# clock.net
KiCad netlist of a schematic drawn in EAGLE
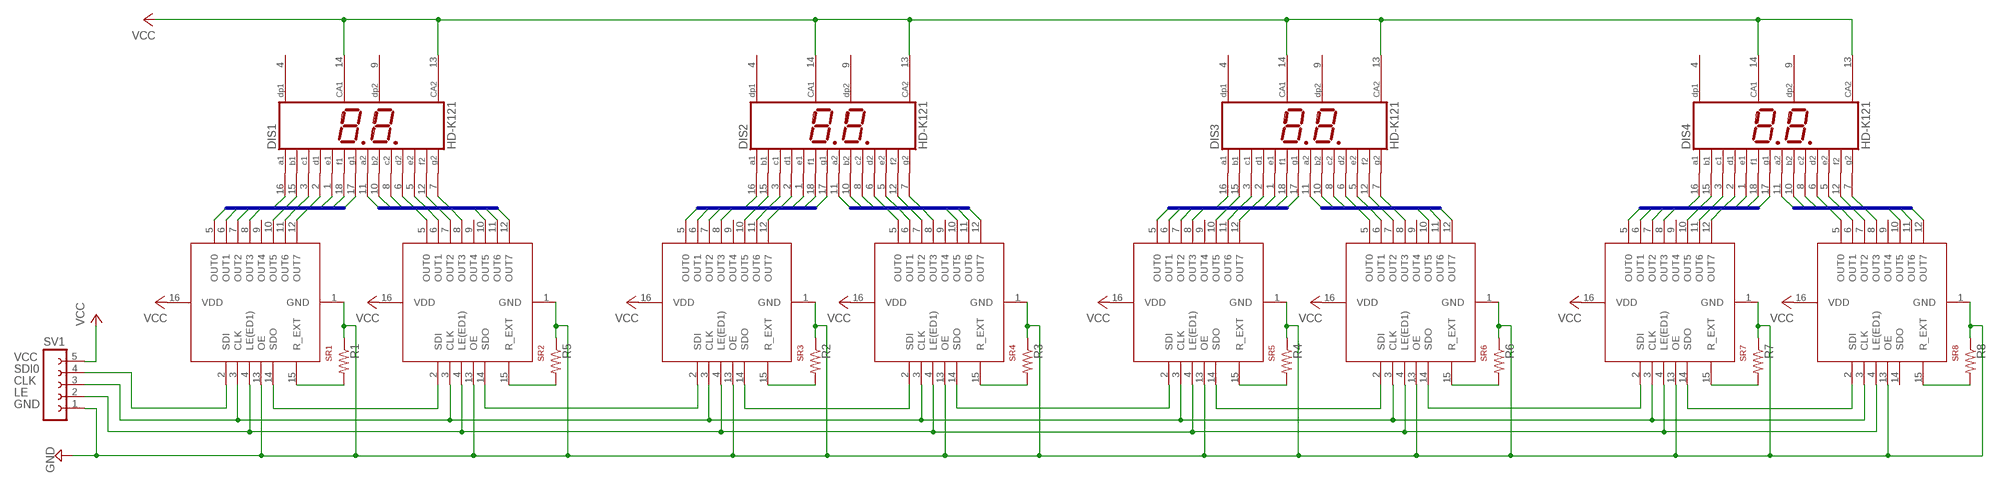
[diagram p0: schematic, sheet 1]

(export (version "E")
  (design (tool "Eeschema 10.0.6"))
  (components
    (comp (ref "DIS1")
      (value "HD-K121")
      (footprint "eagle-import:HDSP-R")
      (libsource (lib "eagle-import") (part "HD-K121"))
    )
    (comp (ref "DIS2")
      (value "HD-K121")
      (footprint "eagle-import:HDSP-R")
      (libsource (lib "eagle-import") (part "HD-K121"))
    )
    (comp (ref "DIS3")
      (value "HD-K121")
      (footprint "eagle-import:HDSP-R")
      (libsource (lib "eagle-import") (part "HD-K121"))
    )
    (comp (ref "DIS4")
      (value "HD-K121")
      (footprint "eagle-import:HDSP-R")
      (libsource (lib "eagle-import") (part "HD-K121"))
    )
    (comp (ref "R1")
      (value "R-US_R0603")
      (footprint "eagle-import:R0603")
      (libsource (lib "eagle-import") (part "R-US_R0603"))
    )
    (comp (ref "R2")
      (value "R-US_R0603")
      (footprint "eagle-import:R0603")
      (libsource (lib "eagle-import") (part "R-US_R0603"))
    )
    (comp (ref "R3")
      (value "R-US_R0603")
      (footprint "eagle-import:R0603")
      (libsource (lib "eagle-import") (part "R-US_R0603"))
    )
    (comp (ref "R4")
      (value "R-US_R0603")
      (footprint "eagle-import:R0603")
      (libsource (lib "eagle-import") (part "R-US_R0603"))
    )
    (comp (ref "R5")
      (value "R-US_R0603")
      (footprint "eagle-import:R0603")
      (libsource (lib "eagle-import") (part "R-US_R0603"))
    )
    (comp (ref "R6")
      (value "R-US_R0603")
      (footprint "eagle-import:R0603")
      (libsource (lib "eagle-import") (part "R-US_R0603"))
    )
    (comp (ref "R7")
      (value "R-US_R0603")
      (footprint "eagle-import:R0603")
      (libsource (lib "eagle-import") (part "R-US_R0603"))
    )
    (comp (ref "R8")
      (value "R-US_R0603")
      (footprint "eagle-import:R0603")
      (libsource (lib "eagle-import") (part "R-US_R0603"))
    )
    (comp (ref "SR1")
      (value "TLC5916/17")
      (footprint "eagle-import:SOIC-16")
      (libsource (lib "eagle-import") (part "TLC5916/17"))
    )
    (comp (ref "SR2")
      (value "TLC5916/17")
      (footprint "eagle-import:SOIC-16")
      (libsource (lib "eagle-import") (part "TLC5916/17"))
    )
    (comp (ref "SR3")
      (value "TLC5916/17")
      (footprint "eagle-import:SOIC-16")
      (libsource (lib "eagle-import") (part "TLC5916/17"))
    )
    (comp (ref "SR4")
      (value "TLC5916/17")
      (footprint "eagle-import:SOIC-16")
      (libsource (lib "eagle-import") (part "TLC5916/17"))
    )
    (comp (ref "SR5")
      (value "TLC5916/17")
      (footprint "eagle-import:SOIC-16")
      (libsource (lib "eagle-import") (part "TLC5916/17"))
    )
    (comp (ref "SR6")
      (value "TLC5916/17")
      (footprint "eagle-import:SOIC-16")
      (libsource (lib "eagle-import") (part "TLC5916/17"))
    )
    (comp (ref "SR7")
      (value "TLC5916/17")
      (footprint "eagle-import:SOIC-16")
      (libsource (lib "eagle-import") (part "TLC5916/17"))
    )
    (comp (ref "SR8")
      (value "TLC5916/17")
      (footprint "eagle-import:SOIC-16")
      (libsource (lib "eagle-import") (part "TLC5916/17"))
    )
    (comp (ref "SV1")
      (value "FE05-1")
      (footprint "eagle-import:FE05-1")
      (libsource (lib "eagle-import") (part "FE05-1"))
    )
  )
  (nets
    (net (code "1") (name "/CLK") (class "Default")
      (node (ref "SR1") (pin "3") (pinfunction "CLK_3") (pintype "bidirectional"))
      (node (ref "SR2") (pin "3") (pinfunction "CLK_3") (pintype "bidirectional"))
      (node (ref "SR3") (pin "3") (pinfunction "CLK_3") (pintype "bidirectional"))
      (node (ref "SR4") (pin "3") (pinfunction "CLK_3") (pintype "bidirectional"))
      (node (ref "SR5") (pin "3") (pinfunction "CLK_3") (pintype "bidirectional"))
      (node (ref "SR6") (pin "3") (pinfunction "CLK_3") (pintype "bidirectional"))
      (node (ref "SR7") (pin "3") (pinfunction "CLK_3") (pintype "bidirectional"))
      (node (ref "SR8") (pin "3") (pinfunction "CLK_3") (pintype "bidirectional"))
      (node (ref "SV1") (pin "3") (pinfunction "3_3") (pintype "passive"))
    )
    (net (code "2") (name "/DAYSONES0") (class "Default")
      (node (ref "DIS1") (pin "11") (pinfunction "A2_11") (pintype "passive"))
      (node (ref "SR2") (pin "11") (pinfunction "OUT6_11") (pintype "bidirectional"))
    )
    (net (code "3") (name "/DAYSONES1") (class "Default")
      (node (ref "DIS1") (pin "10") (pinfunction "B2_10") (pintype "passive"))
      (node (ref "SR2") (pin "12") (pinfunction "OUT7_12") (pintype "bidirectional"))
    )
    (net (code "4") (name "/DAYSONES2") (class "Default")
      (node (ref "DIS1") (pin "8") (pinfunction "C2_8") (pintype "passive"))
      (node (ref "SR2") (pin "5") (pinfunction "OUT0_5") (pintype "bidirectional"))
    )
    (net (code "5") (name "/DAYSONES3") (class "Default")
      (node (ref "DIS1") (pin "6") (pinfunction "D2_6") (pintype "passive"))
      (node (ref "SR2") (pin "7") (pinfunction "OUT2_7") (pintype "bidirectional"))
    )
    (net (code "6") (name "/DAYSONES4") (class "Default")
      (node (ref "DIS1") (pin "5") (pinfunction "E2_5") (pintype "passive"))
      (node (ref "SR2") (pin "8") (pinfunction "OUT3_8") (pintype "bidirectional"))
    )
    (net (code "7") (name "/DAYSONES5") (class "Default")
      (node (ref "DIS1") (pin "12") (pinfunction "F2_12") (pintype "passive"))
      (node (ref "SR2") (pin "10") (pinfunction "OUT5_10") (pintype "bidirectional"))
    )
    (net (code "8") (name "/DAYSONES6") (class "Default")
      (node (ref "DIS1") (pin "7") (pinfunction "G2_7") (pintype "passive"))
      (node (ref "SR2") (pin "6") (pinfunction "OUT1_6") (pintype "bidirectional"))
    )
    (net (code "9") (name "/DAYSTENS0") (class "Default")
      (node (ref "DIS1") (pin "16") (pinfunction "A1_16") (pintype "passive"))
      (node (ref "SR1") (pin "7") (pinfunction "OUT2_7") (pintype "bidirectional"))
    )
    (net (code "10") (name "/DAYSTENS1") (class "Default")
      (node (ref "DIS1") (pin "15") (pinfunction "B1_15") (pintype "passive"))
      (node (ref "SR1") (pin "8") (pinfunction "OUT3_8") (pintype "bidirectional"))
    )
    (net (code "11") (name "/DAYSTENS2") (class "Default")
      (node (ref "DIS1") (pin "3") (pinfunction "C1_3") (pintype "passive"))
      (node (ref "SR1") (pin "10") (pinfunction "OUT5_10") (pintype "bidirectional"))
    )
    (net (code "12") (name "/DAYSTENS3") (class "Default")
      (node (ref "DIS1") (pin "2") (pinfunction "D1_2") (pintype "passive"))
      (node (ref "SR1") (pin "11") (pinfunction "OUT6_11") (pintype "bidirectional"))
    )
    (net (code "13") (name "/DAYSTENS4") (class "Default")
      (node (ref "DIS1") (pin "1") (pinfunction "E1_1") (pintype "passive"))
      (node (ref "SR1") (pin "12") (pinfunction "OUT7_12") (pintype "bidirectional"))
    )
    (net (code "14") (name "/DAYSTENS5") (class "Default")
      (node (ref "DIS1") (pin "18") (pinfunction "F1_18") (pintype "passive"))
      (node (ref "SR1") (pin "5") (pinfunction "OUT0_5") (pintype "bidirectional"))
    )
    (net (code "15") (name "/DAYSTENS6") (class "Default")
      (node (ref "DIS1") (pin "17") (pinfunction "G1_17") (pintype "passive"))
      (node (ref "SR1") (pin "6") (pinfunction "OUT1_6") (pintype "bidirectional"))
    )
    (net (code "16") (name "/HOURSONES0") (class "Default")
      (node (ref "DIS2") (pin "11") (pinfunction "A2_11") (pintype "passive"))
      (node (ref "SR4") (pin "11") (pinfunction "OUT6_11") (pintype "bidirectional"))
    )
    (net (code "17") (name "/HOURSONES1") (class "Default")
      (node (ref "DIS2") (pin "10") (pinfunction "B2_10") (pintype "passive"))
      (node (ref "SR4") (pin "12") (pinfunction "OUT7_12") (pintype "bidirectional"))
    )
    (net (code "18") (name "/HOURSONES2") (class "Default")
      (node (ref "DIS2") (pin "8") (pinfunction "C2_8") (pintype "passive"))
      (node (ref "SR4") (pin "5") (pinfunction "OUT0_5") (pintype "bidirectional"))
    )
    (net (code "19") (name "/HOURSONES3") (class "Default")
      (node (ref "DIS2") (pin "6") (pinfunction "D2_6") (pintype "passive"))
      (node (ref "SR4") (pin "7") (pinfunction "OUT2_7") (pintype "bidirectional"))
    )
    (net (code "20") (name "/HOURSONES4") (class "Default")
      (node (ref "DIS2") (pin "5") (pinfunction "E2_5") (pintype "passive"))
      (node (ref "SR4") (pin "8") (pinfunction "OUT3_8") (pintype "bidirectional"))
    )
    (net (code "21") (name "/HOURSONES5") (class "Default")
      (node (ref "DIS2") (pin "12") (pinfunction "F2_12") (pintype "passive"))
      (node (ref "SR4") (pin "10") (pinfunction "OUT5_10") (pintype "bidirectional"))
    )
    (net (code "22") (name "/HOURSONES6") (class "Default")
      (node (ref "DIS2") (pin "7") (pinfunction "G2_7") (pintype "passive"))
      (node (ref "SR4") (pin "6") (pinfunction "OUT1_6") (pintype "bidirectional"))
    )
    (net (code "23") (name "/HOURSTENS0") (class "Default")
      (node (ref "DIS2") (pin "16") (pinfunction "A1_16") (pintype "passive"))
      (node (ref "SR3") (pin "7") (pinfunction "OUT2_7") (pintype "bidirectional"))
    )
    (net (code "24") (name "/HOURSTENS1") (class "Default")
      (node (ref "DIS2") (pin "15") (pinfunction "B1_15") (pintype "passive"))
      (node (ref "SR3") (pin "8") (pinfunction "OUT3_8") (pintype "bidirectional"))
    )
    (net (code "25") (name "/HOURSTENS2") (class "Default")
      (node (ref "DIS2") (pin "3") (pinfunction "C1_3") (pintype "passive"))
      (node (ref "SR3") (pin "10") (pinfunction "OUT5_10") (pintype "bidirectional"))
    )
    (net (code "26") (name "/HOURSTENS3") (class "Default")
      (node (ref "DIS2") (pin "2") (pinfunction "D1_2") (pintype "passive"))
      (node (ref "SR3") (pin "11") (pinfunction "OUT6_11") (pintype "bidirectional"))
    )
    (net (code "27") (name "/HOURSTENS4") (class "Default")
      (node (ref "DIS2") (pin "1") (pinfunction "E1_1") (pintype "passive"))
      (node (ref "SR3") (pin "12") (pinfunction "OUT7_12") (pintype "bidirectional"))
    )
    (net (code "28") (name "/HOURSTENS5") (class "Default")
      (node (ref "DIS2") (pin "18") (pinfunction "F1_18") (pintype "passive"))
      (node (ref "SR3") (pin "5") (pinfunction "OUT0_5") (pintype "bidirectional"))
    )
    (net (code "29") (name "/HOURSTENS6") (class "Default")
      (node (ref "DIS2") (pin "17") (pinfunction "G1_17") (pintype "passive"))
      (node (ref "SR3") (pin "6") (pinfunction "OUT1_6") (pintype "bidirectional"))
    )
    (net (code "30") (name "/LE") (class "Default")
      (node (ref "SR1") (pin "4") (pinfunction "LE(ED1)_4") (pintype "bidirectional"))
      (node (ref "SR2") (pin "4") (pinfunction "LE(ED1)_4") (pintype "bidirectional"))
      (node (ref "SR3") (pin "4") (pinfunction "LE(ED1)_4") (pintype "bidirectional"))
      (node (ref "SR4") (pin "4") (pinfunction "LE(ED1)_4") (pintype "bidirectional"))
      (node (ref "SR5") (pin "4") (pinfunction "LE(ED1)_4") (pintype "bidirectional"))
      (node (ref "SR6") (pin "4") (pinfunction "LE(ED1)_4") (pintype "bidirectional"))
      (node (ref "SR7") (pin "4") (pinfunction "LE(ED1)_4") (pintype "bidirectional"))
      (node (ref "SR8") (pin "4") (pinfunction "LE(ED1)_4") (pintype "bidirectional"))
      (node (ref "SV1") (pin "2") (pinfunction "2_2") (pintype "passive"))
    )
    (net (code "31") (name "/MINUTESONES0") (class "Default")
      (node (ref "DIS3") (pin "11") (pinfunction "A2_11") (pintype "passive"))
      (node (ref "SR6") (pin "11") (pinfunction "OUT6_11") (pintype "bidirectional"))
    )
    (net (code "32") (name "/MINUTESONES1") (class "Default")
      (node (ref "DIS3") (pin "10") (pinfunction "B2_10") (pintype "passive"))
      (node (ref "SR6") (pin "12") (pinfunction "OUT7_12") (pintype "bidirectional"))
    )
    (net (code "33") (name "/MINUTESONES2") (class "Default")
      (node (ref "DIS3") (pin "8") (pinfunction "C2_8") (pintype "passive"))
      (node (ref "SR6") (pin "5") (pinfunction "OUT0_5") (pintype "bidirectional"))
    )
    (net (code "34") (name "/MINUTESONES3") (class "Default")
      (node (ref "DIS3") (pin "6") (pinfunction "D2_6") (pintype "passive"))
      (node (ref "SR6") (pin "7") (pinfunction "OUT2_7") (pintype "bidirectional"))
    )
    (net (code "35") (name "/MINUTESONES4") (class "Default")
      (node (ref "DIS3") (pin "5") (pinfunction "E2_5") (pintype "passive"))
      (node (ref "SR6") (pin "8") (pinfunction "OUT3_8") (pintype "bidirectional"))
    )
    (net (code "36") (name "/MINUTESONES5") (class "Default")
      (node (ref "DIS3") (pin "12") (pinfunction "F2_12") (pintype "passive"))
      (node (ref "SR6") (pin "10") (pinfunction "OUT5_10") (pintype "bidirectional"))
    )
    (net (code "37") (name "/MINUTESONES6") (class "Default")
      (node (ref "DIS3") (pin "7") (pinfunction "G2_7") (pintype "passive"))
      (node (ref "SR6") (pin "6") (pinfunction "OUT1_6") (pintype "bidirectional"))
    )
    (net (code "38") (name "/MINUTESTENS0") (class "Default")
      (node (ref "DIS3") (pin "16") (pinfunction "A1_16") (pintype "passive"))
      (node (ref "SR5") (pin "7") (pinfunction "OUT2_7") (pintype "bidirectional"))
    )
    (net (code "39") (name "/MINUTESTENS1") (class "Default")
      (node (ref "DIS3") (pin "15") (pinfunction "B1_15") (pintype "passive"))
      (node (ref "SR5") (pin "8") (pinfunction "OUT3_8") (pintype "bidirectional"))
    )
    (net (code "40") (name "/MINUTESTENS2") (class "Default")
      (node (ref "DIS3") (pin "3") (pinfunction "C1_3") (pintype "passive"))
      (node (ref "SR5") (pin "10") (pinfunction "OUT5_10") (pintype "bidirectional"))
    )
    (net (code "41") (name "/MINUTESTENS3") (class "Default")
      (node (ref "DIS3") (pin "2") (pinfunction "D1_2") (pintype "passive"))
      (node (ref "SR5") (pin "11") (pinfunction "OUT6_11") (pintype "bidirectional"))
    )
    (net (code "42") (name "/MINUTESTENS4") (class "Default")
      (node (ref "DIS3") (pin "1") (pinfunction "E1_1") (pintype "passive"))
      (node (ref "SR5") (pin "12") (pinfunction "OUT7_12") (pintype "bidirectional"))
    )
    (net (code "43") (name "/MINUTESTENS5") (class "Default")
      (node (ref "DIS3") (pin "18") (pinfunction "F1_18") (pintype "passive"))
      (node (ref "SR5") (pin "5") (pinfunction "OUT0_5") (pintype "bidirectional"))
    )
    (net (code "44") (name "/MINUTESTENS6") (class "Default")
      (node (ref "DIS3") (pin "17") (pinfunction "G1_17") (pintype "passive"))
      (node (ref "SR5") (pin "6") (pinfunction "OUT1_6") (pintype "bidirectional"))
    )
    (net (code "45") (name "/SDI0") (class "Default")
      (node (ref "SR1") (pin "2") (pinfunction "SDI_2") (pintype "bidirectional"))
      (node (ref "SV1") (pin "4") (pinfunction "4_4") (pintype "passive"))
    )
    (net (code "46") (name "/SECONDSONES0") (class "Default")
      (node (ref "DIS4") (pin "11") (pinfunction "A2_11") (pintype "passive"))
      (node (ref "SR8") (pin "11") (pinfunction "OUT6_11") (pintype "bidirectional"))
    )
    (net (code "47") (name "/SECONDSONES1") (class "Default")
      (node (ref "DIS4") (pin "10") (pinfunction "B2_10") (pintype "passive"))
      (node (ref "SR8") (pin "12") (pinfunction "OUT7_12") (pintype "bidirectional"))
    )
    (net (code "48") (name "/SECONDSONES2") (class "Default")
      (node (ref "DIS4") (pin "8") (pinfunction "C2_8") (pintype "passive"))
      (node (ref "SR8") (pin "5") (pinfunction "OUT0_5") (pintype "bidirectional"))
    )
    (net (code "49") (name "/SECONDSONES3") (class "Default")
      (node (ref "DIS4") (pin "6") (pinfunction "D2_6") (pintype "passive"))
      (node (ref "SR8") (pin "7") (pinfunction "OUT2_7") (pintype "bidirectional"))
    )
    (net (code "50") (name "/SECONDSONES4") (class "Default")
      (node (ref "DIS4") (pin "5") (pinfunction "E2_5") (pintype "passive"))
      (node (ref "SR8") (pin "8") (pinfunction "OUT3_8") (pintype "bidirectional"))
    )
    (net (code "51") (name "/SECONDSONES5") (class "Default")
      (node (ref "DIS4") (pin "12") (pinfunction "F2_12") (pintype "passive"))
      (node (ref "SR8") (pin "10") (pinfunction "OUT5_10") (pintype "bidirectional"))
    )
    (net (code "52") (name "/SECONDSONES6") (class "Default")
      (node (ref "DIS4") (pin "7") (pinfunction "G2_7") (pintype "passive"))
      (node (ref "SR8") (pin "6") (pinfunction "OUT1_6") (pintype "bidirectional"))
    )
    (net (code "53") (name "/SECONDSTENS0") (class "Default")
      (node (ref "DIS4") (pin "16") (pinfunction "A1_16") (pintype "passive"))
      (node (ref "SR7") (pin "7") (pinfunction "OUT2_7") (pintype "bidirectional"))
    )
    (net (code "54") (name "/SECONDSTENS1") (class "Default")
      (node (ref "DIS4") (pin "15") (pinfunction "B1_15") (pintype "passive"))
      (node (ref "SR7") (pin "8") (pinfunction "OUT3_8") (pintype "bidirectional"))
    )
    (net (code "55") (name "/SECONDSTENS2") (class "Default")
      (node (ref "DIS4") (pin "3") (pinfunction "C1_3") (pintype "passive"))
      (node (ref "SR7") (pin "10") (pinfunction "OUT5_10") (pintype "bidirectional"))
    )
    (net (code "56") (name "/SECONDSTENS3") (class "Default")
      (node (ref "DIS4") (pin "2") (pinfunction "D1_2") (pintype "passive"))
      (node (ref "SR7") (pin "11") (pinfunction "OUT6_11") (pintype "bidirectional"))
    )
    (net (code "57") (name "/SECONDSTENS4") (class "Default")
      (node (ref "DIS4") (pin "1") (pinfunction "E1_1") (pintype "passive"))
      (node (ref "SR7") (pin "12") (pinfunction "OUT7_12") (pintype "bidirectional"))
    )
    (net (code "58") (name "/SECONDSTENS5") (class "Default")
      (node (ref "DIS4") (pin "18") (pinfunction "F1_18") (pintype "passive"))
      (node (ref "SR7") (pin "5") (pinfunction "OUT0_5") (pintype "bidirectional"))
    )
    (net (code "59") (name "/SECONDSTENS6") (class "Default")
      (node (ref "DIS4") (pin "17") (pinfunction "G1_17") (pintype "passive"))
      (node (ref "SR7") (pin "6") (pinfunction "OUT1_6") (pintype "bidirectional"))
    )
    (net (code "60") (name "GND") (class "Default")
      (node (ref "R1") (pin "1") (pinfunction "1_1") (pintype "passive"))
      (node (ref "R2") (pin "1") (pinfunction "1_1") (pintype "passive"))
      (node (ref "R3") (pin "1") (pinfunction "1_1") (pintype "passive"))
      (node (ref "R4") (pin "1") (pinfunction "1_1") (pintype "passive"))
      (node (ref "R5") (pin "1") (pinfunction "1_1") (pintype "passive"))
      (node (ref "R6") (pin "1") (pinfunction "1_1") (pintype "passive"))
      (node (ref "R7") (pin "1") (pinfunction "1_1") (pintype "passive"))
      (node (ref "R8") (pin "1") (pinfunction "1_1") (pintype "passive"))
      (node (ref "SR1") (pin "1") (pinfunction "GND_1") (pintype "bidirectional"))
      (node (ref "SR1") (pin "13") (pinfunction "OE_13") (pintype "bidirectional"))
      (node (ref "SR2") (pin "1") (pinfunction "GND_1") (pintype "bidirectional"))
      (node (ref "SR2") (pin "13") (pinfunction "OE_13") (pintype "bidirectional"))
      (node (ref "SR3") (pin "1") (pinfunction "GND_1") (pintype "bidirectional"))
      (node (ref "SR3") (pin "13") (pinfunction "OE_13") (pintype "bidirectional"))
      (node (ref "SR4") (pin "1") (pinfunction "GND_1") (pintype "bidirectional"))
      (node (ref "SR4") (pin "13") (pinfunction "OE_13") (pintype "bidirectional"))
      (node (ref "SR5") (pin "1") (pinfunction "GND_1") (pintype "bidirectional"))
      (node (ref "SR5") (pin "13") (pinfunction "OE_13") (pintype "bidirectional"))
      (node (ref "SR6") (pin "1") (pinfunction "GND_1") (pintype "bidirectional"))
      (node (ref "SR6") (pin "13") (pinfunction "OE_13") (pintype "bidirectional"))
      (node (ref "SR7") (pin "1") (pinfunction "GND_1") (pintype "bidirectional"))
      (node (ref "SR7") (pin "13") (pinfunction "OE_13") (pintype "bidirectional"))
      (node (ref "SR8") (pin "1") (pinfunction "GND_1") (pintype "bidirectional"))
      (node (ref "SR8") (pin "13") (pinfunction "OE_13") (pintype "bidirectional"))
      (node (ref "SV1") (pin "1") (pinfunction "1_1") (pintype "passive"))
    )
    (net (code "61") (name "Net-(SR1-R_EXT)") (class "Default")
      (node (ref "R1") (pin "2") (pinfunction "2_2") (pintype "passive"))
      (node (ref "SR1") (pin "15") (pinfunction "R_EXT_15") (pintype "bidirectional"))
    )
    (net (code "62") (name "Net-(SR1-SDO)") (class "Default")
      (node (ref "SR1") (pin "14") (pinfunction "SDO_14") (pintype "bidirectional"))
      (node (ref "SR2") (pin "2") (pinfunction "SDI_2") (pintype "bidirectional"))
    )
    (net (code "63") (name "Net-(SR2-R_EXT)") (class "Default")
      (node (ref "R5") (pin "2") (pinfunction "2_2") (pintype "passive"))
      (node (ref "SR2") (pin "15") (pinfunction "R_EXT_15") (pintype "bidirectional"))
    )
    (net (code "64") (name "Net-(SR2-SDO)") (class "Default")
      (node (ref "SR2") (pin "14") (pinfunction "SDO_14") (pintype "bidirectional"))
      (node (ref "SR3") (pin "2") (pinfunction "SDI_2") (pintype "bidirectional"))
    )
    (net (code "65") (name "Net-(SR3-R_EXT)") (class "Default")
      (node (ref "R2") (pin "2") (pinfunction "2_2") (pintype "passive"))
      (node (ref "SR3") (pin "15") (pinfunction "R_EXT_15") (pintype "bidirectional"))
    )
    (net (code "66") (name "Net-(SR3-SDO)") (class "Default")
      (node (ref "SR3") (pin "14") (pinfunction "SDO_14") (pintype "bidirectional"))
      (node (ref "SR4") (pin "2") (pinfunction "SDI_2") (pintype "bidirectional"))
    )
    (net (code "67") (name "Net-(SR4-R_EXT)") (class "Default")
      (node (ref "R3") (pin "2") (pinfunction "2_2") (pintype "passive"))
      (node (ref "SR4") (pin "15") (pinfunction "R_EXT_15") (pintype "bidirectional"))
    )
    (net (code "68") (name "Net-(SR4-SDO)") (class "Default")
      (node (ref "SR4") (pin "14") (pinfunction "SDO_14") (pintype "bidirectional"))
      (node (ref "SR5") (pin "2") (pinfunction "SDI_2") (pintype "bidirectional"))
    )
    (net (code "69") (name "Net-(SR5-R_EXT)") (class "Default")
      (node (ref "R4") (pin "2") (pinfunction "2_2") (pintype "passive"))
      (node (ref "SR5") (pin "15") (pinfunction "R_EXT_15") (pintype "bidirectional"))
    )
    (net (code "70") (name "Net-(SR5-SDO)") (class "Default")
      (node (ref "SR5") (pin "14") (pinfunction "SDO_14") (pintype "bidirectional"))
      (node (ref "SR6") (pin "2") (pinfunction "SDI_2") (pintype "bidirectional"))
    )
    (net (code "71") (name "Net-(SR6-R_EXT)") (class "Default")
      (node (ref "R6") (pin "2") (pinfunction "2_2") (pintype "passive"))
      (node (ref "SR6") (pin "15") (pinfunction "R_EXT_15") (pintype "bidirectional"))
    )
    (net (code "72") (name "Net-(SR6-SDO)") (class "Default")
      (node (ref "SR6") (pin "14") (pinfunction "SDO_14") (pintype "bidirectional"))
      (node (ref "SR7") (pin "2") (pinfunction "SDI_2") (pintype "bidirectional"))
    )
    (net (code "73") (name "Net-(SR7-R_EXT)") (class "Default")
      (node (ref "R7") (pin "2") (pinfunction "2_2") (pintype "passive"))
      (node (ref "SR7") (pin "15") (pinfunction "R_EXT_15") (pintype "bidirectional"))
    )
    (net (code "74") (name "Net-(SR7-SDO)") (class "Default")
      (node (ref "SR7") (pin "14") (pinfunction "SDO_14") (pintype "bidirectional"))
      (node (ref "SR8") (pin "2") (pinfunction "SDI_2") (pintype "bidirectional"))
    )
    (net (code "75") (name "Net-(SR8-R_EXT)") (class "Default")
      (node (ref "R8") (pin "2") (pinfunction "2_2") (pintype "passive"))
      (node (ref "SR8") (pin "15") (pinfunction "R_EXT_15") (pintype "bidirectional"))
    )
    (net (code "76") (name "VCC") (class "Default")
      (node (ref "DIS1") (pin "13") (pinfunction "CA2_13") (pintype "passive"))
      (node (ref "DIS1") (pin "14") (pinfunction "CA1_14") (pintype "passive"))
      (node (ref "DIS2") (pin "13") (pinfunction "CA2_13") (pintype "passive"))
      (node (ref "DIS2") (pin "14") (pinfunction "CA1_14") (pintype "passive"))
      (node (ref "DIS3") (pin "13") (pinfunction "CA2_13") (pintype "passive"))
      (node (ref "DIS3") (pin "14") (pinfunction "CA1_14") (pintype "passive"))
      (node (ref "DIS4") (pin "13") (pinfunction "CA2_13") (pintype "passive"))
      (node (ref "DIS4") (pin "14") (pinfunction "CA1_14") (pintype "passive"))
      (node (ref "SR1") (pin "16") (pinfunction "VDD_16") (pintype "bidirectional"))
      (node (ref "SR2") (pin "16") (pinfunction "VDD_16") (pintype "bidirectional"))
      (node (ref "SR3") (pin "16") (pinfunction "VDD_16") (pintype "bidirectional"))
      (node (ref "SR4") (pin "16") (pinfunction "VDD_16") (pintype "bidirectional"))
      (node (ref "SR5") (pin "16") (pinfunction "VDD_16") (pintype "bidirectional"))
      (node (ref "SR6") (pin "16") (pinfunction "VDD_16") (pintype "bidirectional"))
      (node (ref "SR7") (pin "16") (pinfunction "VDD_16") (pintype "bidirectional"))
      (node (ref "SR8") (pin "16") (pinfunction "VDD_16") (pintype "bidirectional"))
      (node (ref "SV1") (pin "5") (pinfunction "5_5") (pintype "passive"))
    )
    (net (code "77") (name "unconnected-(DIS1-DP1-Pad4)") (class "Default")
      (node (ref "DIS1") (pin "4") (pinfunction "DP1_4") (pintype "passive"))
    )
    (net (code "78") (name "unconnected-(DIS1-DP2-Pad9)") (class "Default")
      (node (ref "DIS1") (pin "9") (pinfunction "DP2_9") (pintype "passive"))
    )
    (net (code "79") (name "unconnected-(DIS2-DP1-Pad4)") (class "Default")
      (node (ref "DIS2") (pin "4") (pinfunction "DP1_4") (pintype "passive"))
    )
    (net (code "80") (name "unconnected-(DIS2-DP2-Pad9)") (class "Default")
      (node (ref "DIS2") (pin "9") (pinfunction "DP2_9") (pintype "passive"))
    )
    (net (code "81") (name "unconnected-(DIS3-DP1-Pad4)") (class "Default")
      (node (ref "DIS3") (pin "4") (pinfunction "DP1_4") (pintype "passive"))
    )
    (net (code "82") (name "unconnected-(DIS3-DP2-Pad9)") (class "Default")
      (node (ref "DIS3") (pin "9") (pinfunction "DP2_9") (pintype "passive"))
    )
    (net (code "83") (name "unconnected-(DIS4-DP1-Pad4)") (class "Default")
      (node (ref "DIS4") (pin "4") (pinfunction "DP1_4") (pintype "passive"))
    )
    (net (code "84") (name "unconnected-(DIS4-DP2-Pad9)") (class "Default")
      (node (ref "DIS4") (pin "9") (pinfunction "DP2_9") (pintype "passive"))
    )
    (net (code "85") (name "unconnected-(SR1-OUT4-Pad9)") (class "Default")
      (node (ref "SR1") (pin "9") (pinfunction "OUT4_9") (pintype "bidirectional"))
    )
    (net (code "86") (name "unconnected-(SR2-OUT4-Pad9)") (class "Default")
      (node (ref "SR2") (pin "9") (pinfunction "OUT4_9") (pintype "bidirectional"))
    )
    (net (code "87") (name "unconnected-(SR3-OUT4-Pad9)") (class "Default")
      (node (ref "SR3") (pin "9") (pinfunction "OUT4_9") (pintype "bidirectional"))
    )
    (net (code "88") (name "unconnected-(SR4-OUT4-Pad9)") (class "Default")
      (node (ref "SR4") (pin "9") (pinfunction "OUT4_9") (pintype "bidirectional"))
    )
    (net (code "89") (name "unconnected-(SR5-OUT4-Pad9)") (class "Default")
      (node (ref "SR5") (pin "9") (pinfunction "OUT4_9") (pintype "bidirectional"))
    )
    (net (code "90") (name "unconnected-(SR6-OUT4-Pad9)") (class "Default")
      (node (ref "SR6") (pin "9") (pinfunction "OUT4_9") (pintype "bidirectional"))
    )
    (net (code "91") (name "unconnected-(SR7-OUT4-Pad9)") (class "Default")
      (node (ref "SR7") (pin "9") (pinfunction "OUT4_9") (pintype "bidirectional"))
    )
    (net (code "92") (name "unconnected-(SR8-OUT4-Pad9)") (class "Default")
      (node (ref "SR8") (pin "9") (pinfunction "OUT4_9") (pintype "bidirectional"))
    )
    (net (code "93") (name "unconnected-(SR8-SDO-Pad14)") (class "Default")
      (node (ref "SR8") (pin "14") (pinfunction "SDO_14") (pintype "bidirectional"))
    )
  )
)
